# board.net
KiCad netlist of a schematic drawn in EAGLE
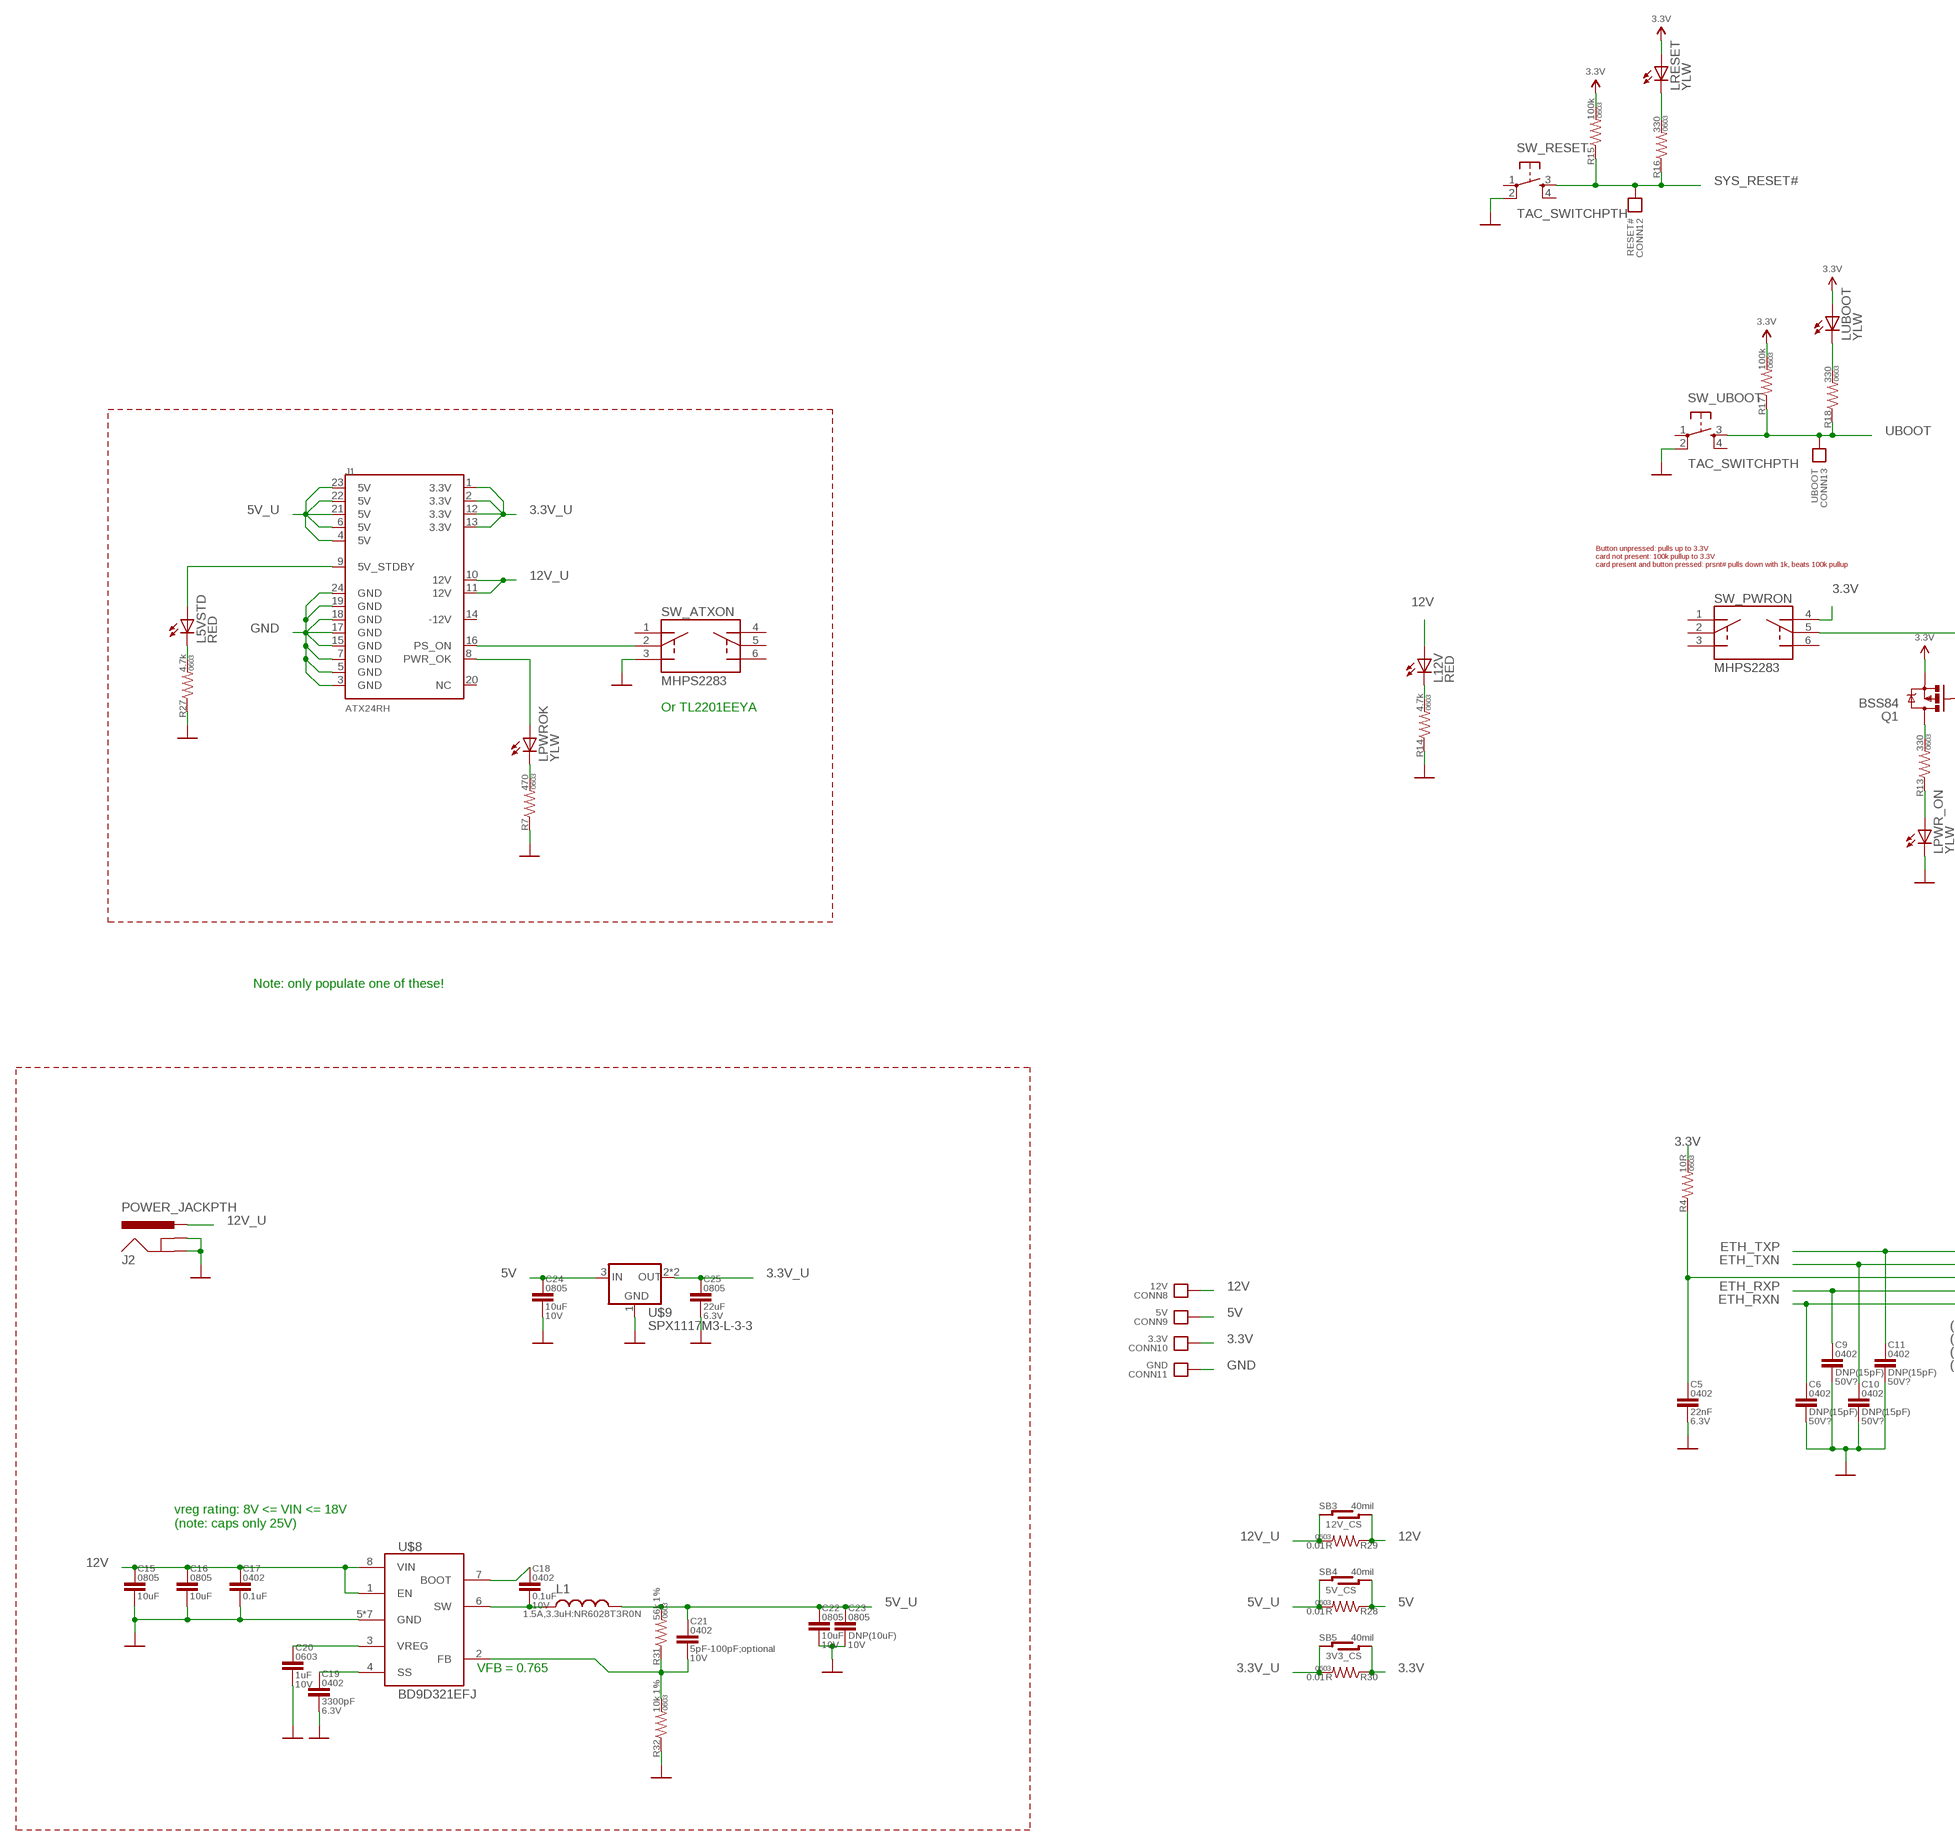
[diagram p0: schematic, sheet 1, part 1 of 2]
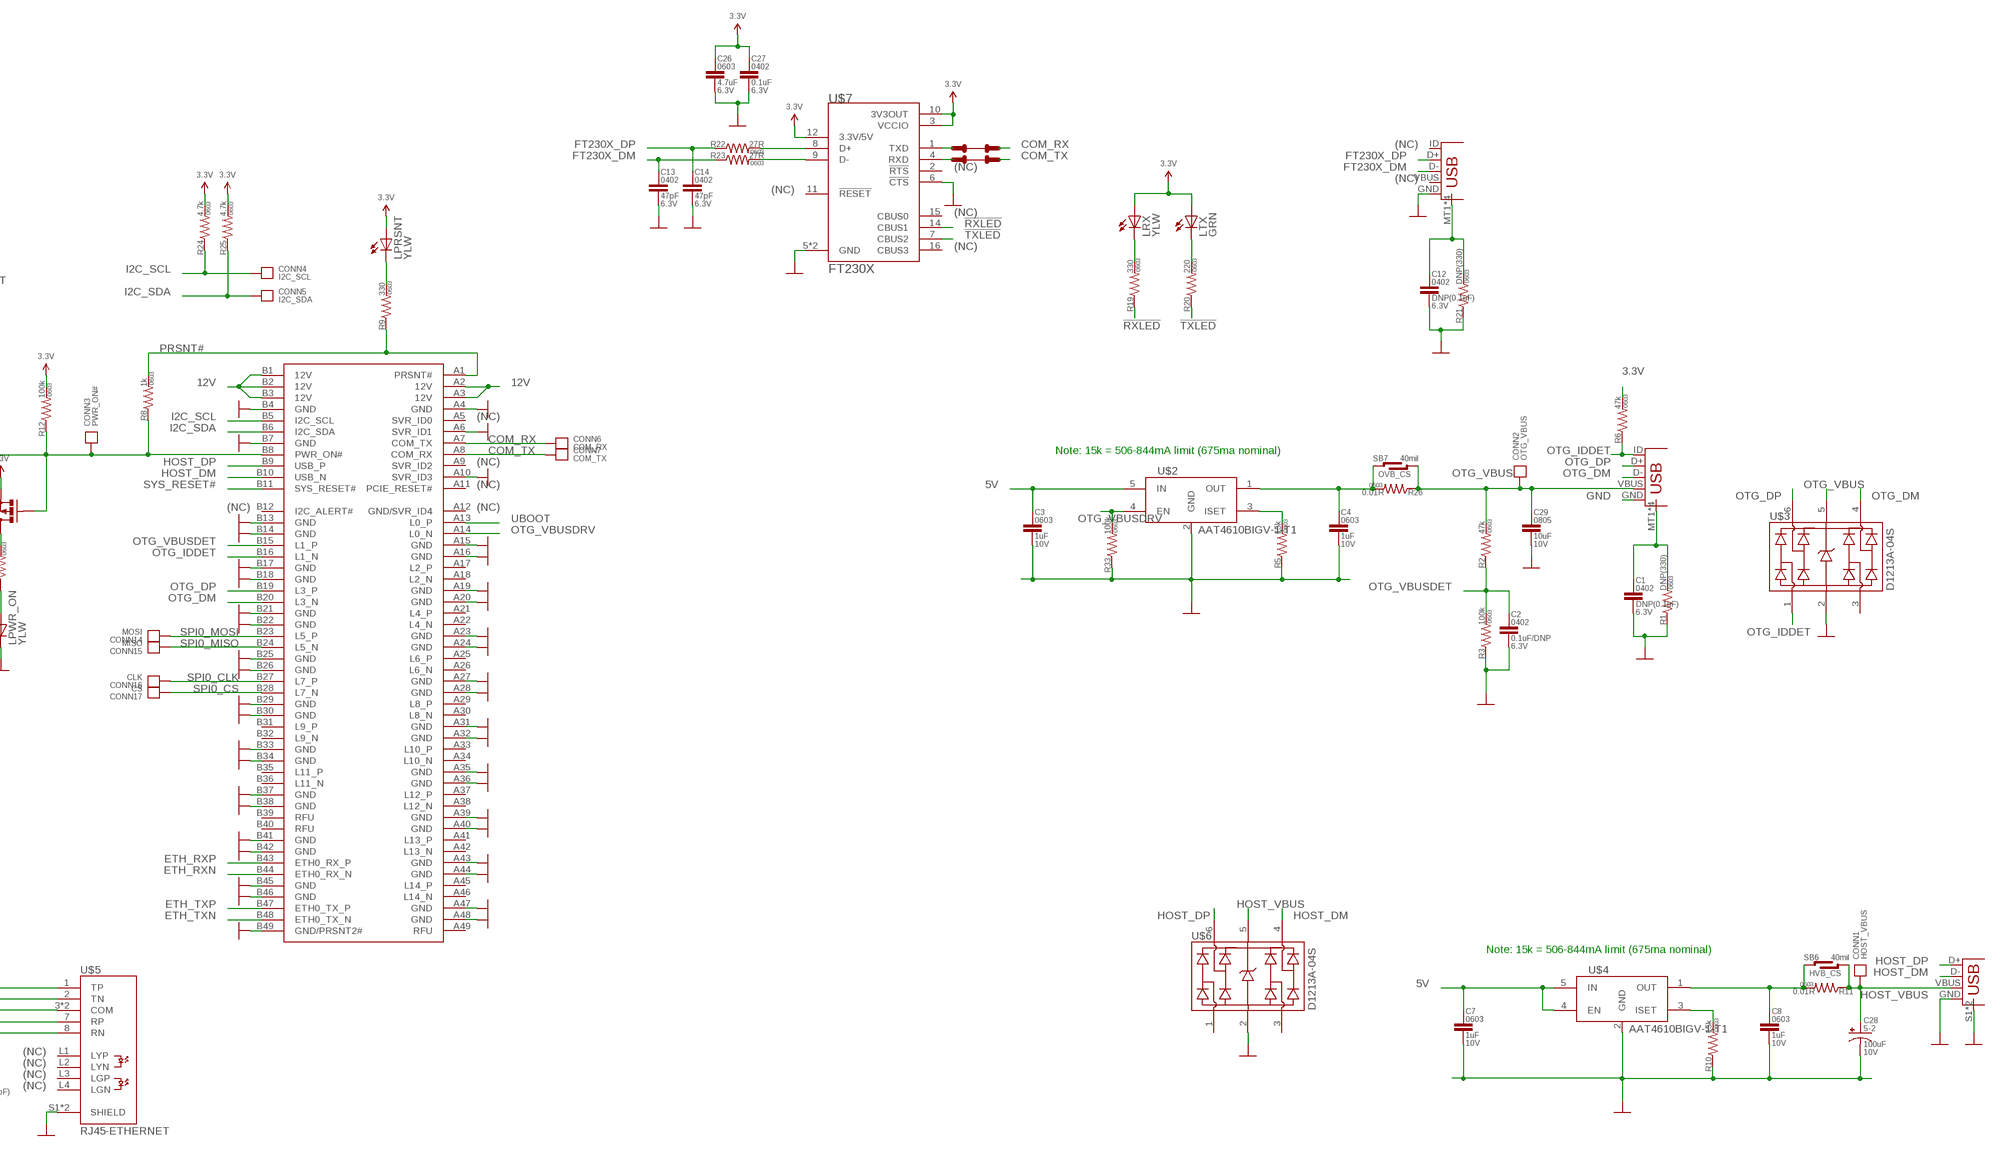
[diagram p1: schematic, sheet 1, part 2 of 2]

(export (version "E")
  (design (tool "Eeschema 10.0.6"))
  (components
    (comp (ref "C1")
      (value "DNP(0.1uF)")
      (footprint "eagle-import:0402-CAP")
      (fields (field (name "VOLTAGE") "6.3V"))
      (libsource (lib "eagle-import") (part "CAP0402-CAP"))
    )
    (comp (ref "C2")
      (value "0.1uF/DNP")
      (footprint "eagle-import:0402-CAP")
      (fields (field (name "VOLTAGE") "6.3V"))
      (libsource (lib "eagle-import") (part "CAP0402-CAP"))
    )
    (comp (ref "C3")
      (value "1uF")
      (footprint "eagle-import:0603-CAP")
      (fields (field (name "VOLTAGE") "6.3V") (field (name "VOLTAGE_1") "10V"))
      (libsource (lib "eagle-import") (part "CAP0603"))
    )
    (comp (ref "C4")
      (value "1uF")
      (footprint "eagle-import:0603-CAP")
      (fields (field (name "VOLTAGE") "6.3V") (field (name "VOLTAGE_1") "10V"))
      (libsource (lib "eagle-import") (part "CAP0603"))
    )
    (comp (ref "C5")
      (value "22nF")
      (footprint "eagle-import:0402-CAP")
      (fields (field (name "VOLTAGE") "6.3V"))
      (libsource (lib "eagle-import") (part "CAP0402-CAP"))
    )
    (comp (ref "C6")
      (value "DNP(15pF)")
      (footprint "eagle-import:0402-CAP")
      (fields (field (name "VOLTAGE") "6.3V") (field (name "VOLTAGE_1") "50V?"))
      (libsource (lib "eagle-import") (part "CAP0402-CAP"))
    )
    (comp (ref "C7")
      (value "1uF")
      (footprint "eagle-import:0603-CAP")
      (fields (field (name "VOLTAGE") "6.3V") (field (name "VOLTAGE_1") "10V"))
      (libsource (lib "eagle-import") (part "CAP0603"))
    )
    (comp (ref "C8")
      (value "1uF")
      (footprint "eagle-import:0603-CAP")
      (fields (field (name "VOLTAGE") "6.3V") (field (name "VOLTAGE_1") "10V"))
      (libsource (lib "eagle-import") (part "CAP0603"))
    )
    (comp (ref "C9")
      (value "DNP(15pF)")
      (footprint "eagle-import:0402-CAP")
      (fields (field (name "VOLTAGE") "6.3V") (field (name "VOLTAGE_1") "50V?"))
      (libsource (lib "eagle-import") (part "CAP0402-CAP"))
    )
    (comp (ref "C10")
      (value "DNP(15pF)")
      (footprint "eagle-import:0402-CAP")
      (fields (field (name "VOLTAGE") "6.3V") (field (name "VOLTAGE_1") "50V?"))
      (libsource (lib "eagle-import") (part "CAP0402-CAP"))
    )
    (comp (ref "C11")
      (value "DNP(15pF)")
      (footprint "eagle-import:0402-CAP")
      (fields (field (name "VOLTAGE") "6.3V") (field (name "VOLTAGE_1") "50V?"))
      (libsource (lib "eagle-import") (part "CAP0402-CAP"))
    )
    (comp (ref "C12")
      (value "DNP(0.1uF)")
      (footprint "eagle-import:0402-CAP")
      (fields (field (name "VOLTAGE") "6.3V"))
      (libsource (lib "eagle-import") (part "CAP0402-CAP"))
    )
    (comp (ref "C13")
      (value "47pF")
      (footprint "eagle-import:0402-CAP")
      (fields (field (name "VOLTAGE") "6.3V"))
      (libsource (lib "eagle-import") (part "CAP0402-CAP"))
    )
    (comp (ref "C14")
      (value "47pF")
      (footprint "eagle-import:0402-CAP")
      (fields (field (name "VOLTAGE") "6.3V"))
      (libsource (lib "eagle-import") (part "CAP0402-CAP"))
    )
    (comp (ref "C15")
      (value "10uF")
      (footprint "eagle-import:0805")
      (fields (field (name "VOLTAGE") "6.3V") (field (name "VOLTAGE_1") "25V"))
      (libsource (lib "eagle-import") (part "CAP0805"))
    )
    (comp (ref "C16")
      (value "10uF")
      (footprint "eagle-import:0805")
      (fields (field (name "VOLTAGE") "6.3V") (field (name "VOLTAGE_1") "25V"))
      (libsource (lib "eagle-import") (part "CAP0805"))
    )
    (comp (ref "C17")
      (value "0.1uF")
      (footprint "eagle-import:0402-CAP")
      (fields (field (name "VOLTAGE") "6.3V") (field (name "VOLTAGE_1") "25V"))
      (libsource (lib "eagle-import") (part "CAP0402-CAP"))
    )
    (comp (ref "C18")
      (value "0.1uF")
      (footprint "eagle-import:0402-CAP")
      (fields (field (name "VOLTAGE") "6.3V") (field (name "VOLTAGE_1") "10V"))
      (libsource (lib "eagle-import") (part "CAP0402-CAP"))
    )
    (comp (ref "C19")
      (value "3300pF")
      (footprint "eagle-import:0402-CAP")
      (fields (field (name "VOLTAGE") "6.3V"))
      (libsource (lib "eagle-import") (part "CAP0402-CAP"))
    )
    (comp (ref "C20")
      (value "1uF")
      (footprint "eagle-import:0603-CAP")
      (fields (field (name "VOLTAGE") "6.3V") (field (name "VOLTAGE_1") "10V"))
      (libsource (lib "eagle-import") (part "CAP0603"))
    )
    (comp (ref "C21")
      (value "5pF-100pF;optional")
      (footprint "eagle-import:0402-CAP")
      (fields (field (name "VOLTAGE") "6.3V") (field (name "VOLTAGE_1") "10V"))
      (libsource (lib "eagle-import") (part "CAP0402-CAP"))
    )
    (comp (ref "C22")
      (value "10uF")
      (footprint "eagle-import:0805")
      (fields (field (name "VOLTAGE") "6.3V") (field (name "VOLTAGE_1") "10V"))
      (libsource (lib "eagle-import") (part "CAP0805"))
    )
    (comp (ref "C23")
      (value "DNP(10uF)")
      (footprint "eagle-import:0805")
      (fields (field (name "VOLTAGE") "6.3V") (field (name "VOLTAGE_1") "10V"))
      (libsource (lib "eagle-import") (part "CAP0805"))
    )
    (comp (ref "C24")
      (value "10uF")
      (footprint "eagle-import:0805")
      (fields (field (name "VOLTAGE") "6.3V") (field (name "VOLTAGE_1") "10V"))
      (libsource (lib "eagle-import") (part "CAP0805"))
    )
    (comp (ref "C25")
      (value "22uF")
      (footprint "eagle-import:0805")
      (fields (field (name "VOLTAGE") "6.3V"))
      (libsource (lib "eagle-import") (part "CAP0805"))
    )
    (comp (ref "C26")
      (value "4.7uF")
      (footprint "eagle-import:0603-CAP")
      (fields (field (name "VOLTAGE") "6.3V"))
      (libsource (lib "eagle-import") (part "CAP0603"))
    )
    (comp (ref "C27")
      (value "0.1uF")
      (footprint "eagle-import:0402-CAP")
      (fields (field (name "VOLTAGE") "6.3V"))
      (libsource (lib "eagle-import") (part "CAP0402-CAP"))
    )
    (comp (ref "C28")
      (value "100uF")
      (footprint "eagle-import:CAP-5-2")
      (fields (field (name "VOLTAGE") "6.3V") (field (name "VOLTAGE_1") "10V"))
      (libsource (lib "eagle-import") (part "CAP_POLPTH-5-2"))
    )
    (comp (ref "C29")
      (value "10uF")
      (footprint "eagle-import:0805")
      (fields (field (name "VOLTAGE") "6.3V") (field (name "VOLTAGE_1") "10V"))
      (libsource (lib "eagle-import") (part "CAP0805"))
    )
    (comp (ref "CONN1")
      (value "HOST_VBUS")
      (footprint "eagle-import:HOLE_22AWG")
      (libsource (lib "eagle-import") (part "CONNECTOR22AWG"))
    )
    (comp (ref "CONN2")
      (value "OTG_VBUS")
      (footprint "eagle-import:HOLE_22AWG")
      (libsource (lib "eagle-import") (part "CONNECTOR22AWG"))
    )
    (comp (ref "CONN3")
      (value "PWR_ON#")
      (footprint "eagle-import:HOLE_22AWG")
      (libsource (lib "eagle-import") (part "CONNECTOR22AWG"))
    )
    (comp (ref "CONN4")
      (value "I2C_SCL")
      (footprint "eagle-import:HOLE_22AWG")
      (libsource (lib "eagle-import") (part "CONNECTOR22AWG"))
    )
    (comp (ref "CONN5")
      (value "I2C_SDA")
      (footprint "eagle-import:HOLE_22AWG")
      (libsource (lib "eagle-import") (part "CONNECTOR22AWG"))
    )
    (comp (ref "CONN6")
      (value "COM_RX")
      (footprint "eagle-import:HOLE_22AWG")
      (libsource (lib "eagle-import") (part "CONNECTOR22AWG"))
    )
    (comp (ref "CONN7")
      (value "COM_TX")
      (footprint "eagle-import:HOLE_22AWG")
      (libsource (lib "eagle-import") (part "CONNECTOR22AWG"))
    )
    (comp (ref "CONN8")
      (value "12V")
      (footprint "eagle-import:HOLE_22AWG")
      (libsource (lib "eagle-import") (part "CONNECTOR22AWG"))
    )
    (comp (ref "CONN9")
      (value "5V")
      (footprint "eagle-import:HOLE_22AWG")
      (libsource (lib "eagle-import") (part "CONNECTOR22AWG"))
    )
    (comp (ref "CONN10")
      (value "3.3V")
      (footprint "eagle-import:HOLE_22AWG")
      (libsource (lib "eagle-import") (part "CONNECTOR22AWG"))
    )
    (comp (ref "CONN11")
      (value "GND")
      (footprint "eagle-import:HOLE_22AWG")
      (libsource (lib "eagle-import") (part "CONNECTOR22AWG"))
    )
    (comp (ref "CONN12")
      (value "RESET#")
      (footprint "eagle-import:HOLE_22AWG")
      (libsource (lib "eagle-import") (part "CONNECTOR22AWG"))
    )
    (comp (ref "CONN13")
      (value "UBOOT")
      (footprint "eagle-import:HOLE_22AWG")
      (libsource (lib "eagle-import") (part "CONNECTOR22AWG"))
    )
    (comp (ref "CONN14")
      (value "MOSI")
      (footprint "eagle-import:HOLE_22AWG")
      (libsource (lib "eagle-import") (part "CONNECTOR22AWG"))
    )
    (comp (ref "CONN15")
      (value "MISO")
      (footprint "eagle-import:HOLE_22AWG")
      (libsource (lib "eagle-import") (part "CONNECTOR22AWG"))
    )
    (comp (ref "CONN16")
      (value "CLK")
      (footprint "eagle-import:HOLE_22AWG")
      (libsource (lib "eagle-import") (part "CONNECTOR22AWG"))
    )
    (comp (ref "CONN17")
      (value "CS")
      (footprint "eagle-import:HOLE_22AWG")
      (libsource (lib "eagle-import") (part "CONNECTOR22AWG"))
    )
    (comp (ref "J1")
      (value "ATX24RH")
      (footprint "eagle-import:ATX24_RIGHT_ANGLE")
      (libsource (lib "eagle-import") (part "ATX24RH"))
    )
    (comp (ref "J2")
      (value "POWER_JACKPTH")
      (footprint "eagle-import:POWER_JACK_PTH")
      (libsource (lib "eagle-import") (part "POWER_JACKPTH"))
    )
    (comp (ref "JP1")
      (value "USB-IDMICRO")
      (footprint "eagle-import:USB-MICRO")
      (libsource (lib "eagle-import") (part "USB-IDMICRO"))
    )
    (comp (ref "JP2")
      (value "USB-IDMICRO")
      (footprint "eagle-import:USB-MICRO")
      (libsource (lib "eagle-import") (part "USB-IDMICRO"))
    )
    (comp (ref "JP3")
      (value "USBA-FEMALE-TH")
      (footprint "eagle-import:USB-A-SOCKET-TH")
      (libsource (lib "eagle-import") (part "USBA-FEMALE-TH"))
    )
    (comp (ref "L1")
      (value "1.5A,3.3uH:NR6028T3R0N")
      (footprint "eagle-import:NR60XX")
      (libsource (lib "eagle-import") (part "INDUCTORNR60XX"))
    )
    (comp (ref "L5VSTD")
      (value "RED")
      (footprint "eagle-import:0603_LED")
      (libsource (lib "eagle-import") (part "LED0603"))
    )
    (comp (ref "L12V")
      (value "RED")
      (footprint "eagle-import:0603_LED")
      (libsource (lib "eagle-import") (part "LED0603"))
    )
    (comp (ref "LPRSNT")
      (value "YLW")
      (footprint "eagle-import:0603_LED")
      (libsource (lib "eagle-import") (part "LED0603"))
    )
    (comp (ref "LPWROK")
      (value "YLW")
      (footprint "eagle-import:0603_LED")
      (libsource (lib "eagle-import") (part "LED0603"))
    )
    (comp (ref "LPWR_ON")
      (value "YLW")
      (footprint "eagle-import:0603_LED")
      (libsource (lib "eagle-import") (part "LED0603"))
    )
    (comp (ref "LRESET")
      (value "YLW")
      (footprint "eagle-import:0603_LED")
      (libsource (lib "eagle-import") (part "LED0603"))
    )
    (comp (ref "LRX")
      (value "YLW")
      (footprint "eagle-import:0603_LED")
      (libsource (lib "eagle-import") (part "LED0603"))
    )
    (comp (ref "LTX")
      (value "GRN")
      (footprint "eagle-import:0603_LED")
      (libsource (lib "eagle-import") (part "LED0603"))
    )
    (comp (ref "LUBOOT")
      (value "YLW")
      (footprint "eagle-import:0603_LED")
      (libsource (lib "eagle-import") (part "LED0603"))
    )
    (comp (ref "Q1")
      (value "BSS84")
      (footprint "eagle-import:SOT23-3")
      (libsource (lib "eagle-import") (part "MOSFET-PCHANNELSMD"))
    )
    (comp (ref "R1")
      (value "DNP(330)")
      (footprint "eagle-import:0603-RES")
      (libsource (lib "eagle-import") (part "RESISTOR0603"))
    )
    (comp (ref "R2")
      (value "47k")
      (footprint "eagle-import:0603-RES")
      (libsource (lib "eagle-import") (part "RESISTOR0603"))
    )
    (comp (ref "R3")
      (value "100k")
      (footprint "eagle-import:0603-RES")
      (libsource (lib "eagle-import") (part "RESISTOR0603"))
    )
    (comp (ref "R4")
      (value "10R")
      (footprint "eagle-import:0603-RES")
      (libsource (lib "eagle-import") (part "RESISTOR0603"))
    )
    (comp (ref "R5")
      (value "15k")
      (footprint "eagle-import:0603-RES")
      (libsource (lib "eagle-import") (part "RESISTOR0603"))
    )
    (comp (ref "R6")
      (value "47k")
      (footprint "eagle-import:0603-RES")
      (libsource (lib "eagle-import") (part "RESISTOR0603"))
    )
    (comp (ref "R7")
      (value "470")
      (footprint "eagle-import:0603-RES")
      (libsource (lib "eagle-import") (part "RESISTOR0603"))
    )
    (comp (ref "R8")
      (value "1k")
      (footprint "eagle-import:0603-RES")
      (libsource (lib "eagle-import") (part "RESISTOR0603"))
    )
    (comp (ref "R9")
      (value "330")
      (footprint "eagle-import:0603-RES")
      (libsource (lib "eagle-import") (part "RESISTOR0603"))
    )
    (comp (ref "R10")
      (value "15k")
      (footprint "eagle-import:0603-RES")
      (libsource (lib "eagle-import") (part "RESISTOR0603"))
    )
    (comp (ref "R11")
      (value "0.01R")
      (footprint "eagle-import:0603-RES")
      (libsource (lib "eagle-import") (part "RESISTOR0603"))
    )
    (comp (ref "R12")
      (value "100k")
      (footprint "eagle-import:0603-RES")
      (libsource (lib "eagle-import") (part "RESISTOR0603"))
    )
    (comp (ref "R13")
      (value "330")
      (footprint "eagle-import:0603-RES")
      (libsource (lib "eagle-import") (part "RESISTOR0603"))
    )
    (comp (ref "R14")
      (value "4.7k")
      (footprint "eagle-import:0603-RES")
      (libsource (lib "eagle-import") (part "RESISTOR0603"))
    )
    (comp (ref "R15")
      (value "100k")
      (footprint "eagle-import:0603-RES")
      (libsource (lib "eagle-import") (part "RESISTOR0603"))
    )
    (comp (ref "R16")
      (value "330")
      (footprint "eagle-import:0603-RES")
      (libsource (lib "eagle-import") (part "RESISTOR0603"))
    )
    (comp (ref "R17")
      (value "100k")
      (footprint "eagle-import:0603-RES")
      (libsource (lib "eagle-import") (part "RESISTOR0603"))
    )
    (comp (ref "R18")
      (value "330")
      (footprint "eagle-import:0603-RES")
      (libsource (lib "eagle-import") (part "RESISTOR0603"))
    )
    (comp (ref "R19")
      (value "330")
      (footprint "eagle-import:0603-RES")
      (libsource (lib "eagle-import") (part "RESISTOR0603"))
    )
    (comp (ref "R20")
      (value "220")
      (footprint "eagle-import:0603-RES")
      (libsource (lib "eagle-import") (part "RESISTOR0603"))
    )
    (comp (ref "R21")
      (value "DNP(330)")
      (footprint "eagle-import:0603-RES")
      (libsource (lib "eagle-import") (part "RESISTOR0603"))
    )
    (comp (ref "R22")
      (value "27R")
      (footprint "eagle-import:0603-RES")
      (libsource (lib "eagle-import") (part "RESISTOR0603"))
    )
    (comp (ref "R23")
      (value "27R")
      (footprint "eagle-import:0603-RES")
      (libsource (lib "eagle-import") (part "RESISTOR0603"))
    )
    (comp (ref "R24")
      (value "4.7k")
      (footprint "eagle-import:0603-RES")
      (libsource (lib "eagle-import") (part "RESISTOR0603"))
    )
    (comp (ref "R25")
      (value "4.7k")
      (footprint "eagle-import:0603-RES")
      (libsource (lib "eagle-import") (part "RESISTOR0603"))
    )
    (comp (ref "R26")
      (value "0.01R")
      (footprint "eagle-import:0603-RES")
      (libsource (lib "eagle-import") (part "RESISTOR0603"))
    )
    (comp (ref "R27")
      (value "4.7k")
      (footprint "eagle-import:0603-RES")
      (libsource (lib "eagle-import") (part "RESISTOR0603"))
    )
    (comp (ref "R28")
      (value "0.01R")
      (footprint "eagle-import:0603-RES")
      (libsource (lib "eagle-import") (part "RESISTOR0603"))
    )
    (comp (ref "R29")
      (value "0.01R")
      (footprint "eagle-import:0603-RES")
      (libsource (lib "eagle-import") (part "RESISTOR0603"))
    )
    (comp (ref "R30")
      (value "0.01R")
      (footprint "eagle-import:0603-RES")
      (libsource (lib "eagle-import") (part "RESISTOR0603"))
    )
    (comp (ref "R31")
      (value "56k 1%")
      (footprint "eagle-import:0603-RES")
      (libsource (lib "eagle-import") (part "RESISTOR0603"))
    )
    (comp (ref "R32")
      (value "10k 1%")
      (footprint "eagle-import:0603-RES")
      (libsource (lib "eagle-import") (part "RESISTOR0603"))
    )
    (comp (ref "R33")
      (value "100k")
      (footprint "eagle-import:0603-RES")
      (libsource (lib "eagle-import") (part "RESISTOR0603"))
    )
    (comp (ref "SB1")
      (value "RX")
      (footprint "eagle-import:TRACE-CUT")
      (libsource (lib "eagle-import") (part "TRACE-CUT"))
    )
    (comp (ref "SB2")
      (value "TX")
      (footprint "eagle-import:TRACE-CUT")
      (libsource (lib "eagle-import") (part "TRACE-CUT"))
    )
    (comp (ref "SB3")
      (value "12V_CS")
      (footprint "eagle-import:SOLDER-BRIDGE-OPEN-LARGE")
      (libsource (lib "eagle-import") (part "SOLDER-BRIDGEOPEN-WIDE"))
    )
    (comp (ref "SB4")
      (value "5V_CS")
      (footprint "eagle-import:SOLDER-BRIDGE-OPEN-LARGE")
      (libsource (lib "eagle-import") (part "SOLDER-BRIDGEOPEN-WIDE"))
    )
    (comp (ref "SB5")
      (value "3V3_CS")
      (footprint "eagle-import:SOLDER-BRIDGE-OPEN-LARGE")
      (libsource (lib "eagle-import") (part "SOLDER-BRIDGEOPEN-WIDE"))
    )
    (comp (ref "SB6")
      (value "HVB_CS")
      (footprint "eagle-import:SOLDER-BRIDGE-OPEN-LARGE")
      (libsource (lib "eagle-import") (part "SOLDER-BRIDGEOPEN-WIDE"))
    )
    (comp (ref "SB7")
      (value "OVB_CS")
      (footprint "eagle-import:SOLDER-BRIDGE-OPEN-LARGE")
      (libsource (lib "eagle-import") (part "SOLDER-BRIDGEOPEN-WIDE"))
    )
    (comp (ref "SW_ATXON")
      (value "MHPS2283")
      (footprint "eagle-import:PUSHBUTTON-2.5-5.4")
      (libsource (lib "eagle-import") (part "SWITCH_DPDTPUSHBUTTON"))
    )
    (comp (ref "SW_PWRON")
      (value "MHPS2283")
      (footprint "eagle-import:PUSHBUTTON-2.5-5.4")
      (libsource (lib "eagle-import") (part "SWITCH_DPDTPUSHBUTTON"))
    )
    (comp (ref "SW_RESET")
      (value "TAC_SWITCHPTH")
      (footprint "eagle-import:TACTILE-PTH")
      (libsource (lib "eagle-import") (part "TAC_SWITCHPTH"))
    )
    (comp (ref "SW_UBOOT")
      (value "TAC_SWITCHPTH")
      (footprint "eagle-import:TACTILE-PTH")
      (libsource (lib "eagle-import") (part "TAC_SWITCHPTH"))
    )
    (comp (ref "U$1")
      (value "CVN-V1CONN")
      (footprint "eagle-import:CVN-V1-CONN")
      (libsource (lib "eagle-import") (part "CVN-V1CONN"))
    )
    (comp (ref "U$2")
      (value "AAT4610BIGV-1-T1")
      (footprint "eagle-import:SOT23-5")
      (libsource (lib "eagle-import") (part "LOAD_SWITCH_ILIMIT"))
    )
    (comp (ref "U$3")
      (value "D1213A-04S")
      (footprint "eagle-import:SOT363")
      (libsource (lib "eagle-import") (part "TVS_ARRAY"))
    )
    (comp (ref "U$4")
      (value "AAT4610BIGV-1-T1")
      (footprint "eagle-import:SOT23-5")
      (libsource (lib "eagle-import") (part "LOAD_SWITCH_ILIMIT"))
    )
    (comp (ref "U$5")
      (value "RJ45-ETHERNET")
      (footprint "eagle-import:RJ45")
      (libsource (lib "eagle-import") (part "RJ45-ETHERNET"))
    )
    (comp (ref "U$6")
      (value "D1213A-04S")
      (footprint "eagle-import:SOT363")
      (libsource (lib "eagle-import") (part "TVS_ARRAY"))
    )
    (comp (ref "U$7")
      (value "FT230X")
      (footprint "eagle-import:TSSOP16")
      (libsource (lib "eagle-import") (part "FT230X"))
    )
    (comp (ref "U$8")
      (value "BD9D321EFJ")
      (footprint "eagle-import:HTSOP8")
      (libsource (lib "eagle-import") (part "BD9D321EFJ"))
    )
    (comp (ref "U$9")
      (value "SPX1117M3-L-3-3")
      (footprint "eagle-import:SOT223")
      (libsource (lib "eagle-import") (part "VREGSOT223"))
    )
  )
  (nets
    (net (code "1") (name "/3.3V_U") (class "Default")
      (node (ref "C25") (pin "1") (pinfunction "1_1") (pintype "passive"))
      (node (ref "J1") (pin "1") (pinfunction "3.3V_1") (pintype "bidirectional"))
      (node (ref "J1") (pin "12") (pinfunction "3.3V_12") (pintype "bidirectional"))
      (node (ref "J1") (pin "13") (pinfunction "3.3V_13") (pintype "bidirectional"))
      (node (ref "J1") (pin "2") (pinfunction "3.3V_2") (pintype "bidirectional"))
      (node (ref "R30") (pin "2") (pinfunction "2_2") (pintype "passive"))
      (node (ref "SB5") (pin "L1") (pinfunction "P$1_L1") (pintype "passive"))
      (node (ref "SB5") (pin "L2") (pinfunction "P$1_L2") (pintype "passive"))
      (node (ref "U$9") (pin "2") (pinfunction "OUT_2") (pintype "passive"))
      (node (ref "U$9") (pin "4") (pinfunction "OUT_4") (pintype "passive"))
    )
    (net (code "2") (name "/5V") (class "Default")
      (node (ref "C24") (pin "1") (pinfunction "1_1") (pintype "passive"))
      (node (ref "C3") (pin "1") (pinfunction "1_1") (pintype "passive"))
      (node (ref "C7") (pin "1") (pinfunction "1_1") (pintype "passive"))
      (node (ref "CONN9") (pin "P") (pinfunction "P_P") (pintype "bidirectional"))
      (node (ref "R28") (pin "1") (pinfunction "1_1") (pintype "passive"))
      (node (ref "SB4") (pin "R1") (pinfunction "P$2_R1") (pintype "passive"))
      (node (ref "SB4") (pin "R2") (pinfunction "P$2_R2") (pintype "passive"))
      (node (ref "U$2") (pin "5") (pinfunction "IN_5") (pintype "bidirectional"))
      (node (ref "U$4") (pin "4") (pinfunction "EN_4") (pintype "bidirectional"))
      (node (ref "U$4") (pin "5") (pinfunction "IN_5") (pintype "bidirectional"))
      (node (ref "U$9") (pin "3") (pinfunction "IN_3") (pintype "input"))
    )
    (net (code "3") (name "/5V_U") (class "Default")
      (node (ref "C21") (pin "1") (pinfunction "1_1") (pintype "passive"))
      (node (ref "C22") (pin "1") (pinfunction "1_1") (pintype "passive"))
      (node (ref "C23") (pin "1") (pinfunction "1_1") (pintype "passive"))
      (node (ref "J1") (pin "21") (pinfunction "5V_21") (pintype "bidirectional"))
      (node (ref "J1") (pin "22") (pinfunction "5V_22") (pintype "bidirectional"))
      (node (ref "J1") (pin "23") (pinfunction "5V_23") (pintype "bidirectional"))
      (node (ref "J1") (pin "4") (pinfunction "5V_4") (pintype "bidirectional"))
      (node (ref "J1") (pin "6") (pinfunction "5V_6") (pintype "bidirectional"))
      (node (ref "L1") (pin "P$2") (pinfunction "2_P$2") (pintype "passive"))
      (node (ref "R28") (pin "2") (pinfunction "2_2") (pintype "passive"))
      (node (ref "R31") (pin "2") (pinfunction "2_2") (pintype "passive"))
      (node (ref "SB4") (pin "L1") (pinfunction "P$1_L1") (pintype "passive"))
      (node (ref "SB4") (pin "L2") (pinfunction "P$1_L2") (pintype "passive"))
    )
    (net (code "4") (name "/12V") (class "Default")
      (node (ref "C15") (pin "1") (pinfunction "1_1") (pintype "passive"))
      (node (ref "C16") (pin "1") (pinfunction "1_1") (pintype "passive"))
      (node (ref "C17") (pin "1") (pinfunction "1_1") (pintype "passive"))
      (node (ref "CONN8") (pin "P") (pinfunction "P_P") (pintype "bidirectional"))
      (node (ref "L12V") (pin "A") (pinfunction "A_A") (pintype "passive"))
      (node (ref "R29") (pin "1") (pinfunction "1_1") (pintype "passive"))
      (node (ref "SB3") (pin "R1") (pinfunction "P$2_R1") (pintype "passive"))
      (node (ref "SB3") (pin "R2") (pinfunction "P$2_R2") (pintype "passive"))
      (node (ref "U$1") (pin "A2") (pinfunction "12V_A2") (pintype "input"))
      (node (ref "U$1") (pin "A3") (pinfunction "12V_A3") (pintype "input"))
      (node (ref "U$1") (pin "B1") (pinfunction "12V_B1") (pintype "input"))
      (node (ref "U$1") (pin "B2") (pinfunction "12V_B2") (pintype "input"))
      (node (ref "U$1") (pin "B3") (pinfunction "12V_B3") (pintype "input"))
      (node (ref "U$8") (pin "1") (pinfunction "EN_1") (pintype "input"))
      (node (ref "U$8") (pin "8") (pinfunction "VIN_8") (pintype "input"))
    )
    (net (code "5") (name "/12V_U") (class "Default")
      (node (ref "J1") (pin "10") (pinfunction "12V_10") (pintype "bidirectional"))
      (node (ref "J1") (pin "11") (pinfunction "12V_11") (pintype "bidirectional"))
      (node (ref "J2") (pin "PWR") (pinfunction "PWR_PWR") (pintype "bidirectional"))
      (node (ref "R29") (pin "2") (pinfunction "2_2") (pintype "passive"))
      (node (ref "SB3") (pin "L1") (pinfunction "P$1_L1") (pintype "passive"))
      (node (ref "SB3") (pin "L2") (pinfunction "P$1_L2") (pintype "passive"))
    )
    (net (code "6") (name "/COM_RX") (class "Default")
      (node (ref "CONN6") (pin "P") (pinfunction "P_P") (pintype "bidirectional"))
      (node (ref "SB1") (pin "R1") (pinfunction "P$2_R1") (pintype "passive"))
      (node (ref "U$1") (pin "A7") (pinfunction "COM_TX_A7") (pintype "bidirectional"))
    )
    (net (code "7") (name "/COM_TX") (class "Default")
      (node (ref "CONN7") (pin "P") (pinfunction "P_P") (pintype "bidirectional"))
      (node (ref "SB2") (pin "R1") (pinfunction "P$2_R1") (pintype "passive"))
      (node (ref "U$1") (pin "A8") (pinfunction "COM_RX_A8") (pintype "bidirectional"))
    )
    (net (code "8") (name "/ETH_RXN") (class "Default")
      (node (ref "C6") (pin "1") (pinfunction "1_1") (pintype "passive"))
      (node (ref "U$1") (pin "B44") (pinfunction "ETH0_RX_N_B44") (pintype "bidirectional"))
      (node (ref "U$5") (pin "8") (pinfunction "RN_8") (pintype "bidirectional"))
    )
    (net (code "9") (name "/ETH_RXP") (class "Default")
      (node (ref "C9") (pin "1") (pinfunction "1_1") (pintype "passive"))
      (node (ref "U$1") (pin "B43") (pinfunction "ETH0_RX_P_B43") (pintype "bidirectional"))
      (node (ref "U$5") (pin "7") (pinfunction "RP_7") (pintype "bidirectional"))
    )
    (net (code "10") (name "/ETH_TXN") (class "Default")
      (node (ref "C10") (pin "1") (pinfunction "1_1") (pintype "passive"))
      (node (ref "U$1") (pin "B48") (pinfunction "ETH0_TX_N_B48") (pintype "bidirectional"))
      (node (ref "U$5") (pin "2") (pinfunction "TN_2") (pintype "bidirectional"))
    )
    (net (code "11") (name "/ETH_TXP") (class "Default")
      (node (ref "C11") (pin "1") (pinfunction "1_1") (pintype "passive"))
      (node (ref "U$1") (pin "B47") (pinfunction "ETH0_TX_P_B47") (pintype "bidirectional"))
      (node (ref "U$5") (pin "1") (pinfunction "TP_1") (pintype "bidirectional"))
    )
    (net (code "12") (name "/FT230X_DM") (class "Default")
      (node (ref "C13") (pin "1") (pinfunction "1_1") (pintype "passive"))
      (node (ref "JP2") (pin "D-") (pinfunction "D-_D-") (pintype "bidirectional"))
      (node (ref "R23") (pin "1") (pinfunction "1_1") (pintype "passive"))
    )
    (net (code "13") (name "/FT230X_DP") (class "Default")
      (node (ref "C14") (pin "1") (pinfunction "1_1") (pintype "passive"))
      (node (ref "JP2") (pin "D+") (pinfunction "D+_D+") (pintype "bidirectional"))
      (node (ref "R22") (pin "1") (pinfunction "1_1") (pintype "passive"))
    )
    (net (code "14") (name "/HOST_DM") (class "Default")
      (node (ref "JP3") (pin "D-") (pinfunction "D-_D-") (pintype "bidirectional"))
      (node (ref "U$1") (pin "B10") (pinfunction "USB_N_B10") (pintype "bidirectional"))
      (node (ref "U$6") (pin "4") (pinfunction "CH3_4") (pintype "bidirectional"))
    )
    (net (code "15") (name "/HOST_DP") (class "Default")
      (node (ref "JP3") (pin "D+") (pinfunction "D+_D+") (pintype "bidirectional"))
      (node (ref "U$1") (pin "B9") (pinfunction "USB_P_B9") (pintype "bidirectional"))
      (node (ref "U$6") (pin "6") (pinfunction "CH4_6") (pintype "bidirectional"))
    )
    (net (code "16") (name "/HOST_VBUS") (class "Default")
      (node (ref "C28") (pin "1") (pinfunction "+_1") (pintype "passive"))
      (node (ref "CONN1") (pin "P") (pinfunction "P_P") (pintype "bidirectional"))
      (node (ref "JP3") (pin "VBUS") (pinfunction "VBUS_VBUS") (pintype "bidirectional"))
      (node (ref "R11") (pin "1") (pinfunction "1_1") (pintype "passive"))
      (node (ref "SB6") (pin "R1") (pinfunction "P$2_R1") (pintype "passive"))
      (node (ref "SB6") (pin "R2") (pinfunction "P$2_R2") (pintype "passive"))
      (node (ref "U$6") (pin "5") (pinfunction "VP_5") (pintype "bidirectional"))
    )
    (net (code "17") (name "/I2C_SCL") (class "Default")
      (node (ref "CONN4") (pin "P") (pinfunction "P_P") (pintype "bidirectional"))
      (node (ref "R24") (pin "1") (pinfunction "1_1") (pintype "passive"))
      (node (ref "U$1") (pin "B5") (pinfunction "I2C_SCL_B5") (pintype "bidirectional"))
    )
    (net (code "18") (name "/I2C_SDA") (class "Default")
      (node (ref "CONN5") (pin "P") (pinfunction "P_P") (pintype "bidirectional"))
      (node (ref "R25") (pin "1") (pinfunction "1_1") (pintype "passive"))
      (node (ref "U$1") (pin "B6") (pinfunction "I2C_SDA_B6") (pintype "bidirectional"))
    )
    (net (code "19") (name "/OTG_DM") (class "Default")
      (node (ref "JP1") (pin "D-") (pinfunction "D-_D-") (pintype "bidirectional"))
      (node (ref "U$1") (pin "B20") (pinfunction "L3_N_B20") (pintype "bidirectional"))
      (node (ref "U$3") (pin "4") (pinfunction "CH3_4") (pintype "bidirectional"))
    )
    (net (code "20") (name "/OTG_DP") (class "Default")
      (node (ref "JP1") (pin "D+") (pinfunction "D+_D+") (pintype "bidirectional"))
      (node (ref "U$1") (pin "B19") (pinfunction "L3_P_B19") (pintype "bidirectional"))
      (node (ref "U$3") (pin "6") (pinfunction "CH4_6") (pintype "bidirectional"))
    )
    (net (code "21") (name "/OTG_IDDET") (class "Default")
      (node (ref "JP1") (pin "ID") (pinfunction "ID_ID") (pintype "bidirectional"))
      (node (ref "R6") (pin "1") (pinfunction "1_1") (pintype "passive"))
      (node (ref "U$1") (pin "B16") (pinfunction "L1_N_B16") (pintype "bidirectional"))
      (node (ref "U$3") (pin "1") (pinfunction "CH1_1") (pintype "bidirectional"))
    )
    (net (code "22") (name "/OTG_VBUS") (class "Default")
      (node (ref "C29") (pin "1") (pinfunction "1_1") (pintype "passive"))
      (node (ref "CONN2") (pin "P") (pinfunction "P_P") (pintype "bidirectional"))
      (node (ref "JP1") (pin "VBUS") (pinfunction "VBUS_VBUS") (pintype "bidirectional"))
      (node (ref "R2") (pin "2") (pinfunction "2_2") (pintype "passive"))
      (node (ref "R26") (pin "1") (pinfunction "1_1") (pintype "passive"))
      (node (ref "SB7") (pin "R1") (pinfunction "P$2_R1") (pintype "passive"))
      (node (ref "SB7") (pin "R2") (pinfunction "P$2_R2") (pintype "passive"))
      (node (ref "U$3") (pin "5") (pinfunction "VP_5") (pintype "bidirectional"))
    )
    (net (code "23") (name "/OTG_VBUSDET") (class "Default")
      (node (ref "C2") (pin "1") (pinfunction "1_1") (pintype "passive"))
      (node (ref "R2") (pin "1") (pinfunction "1_1") (pintype "passive"))
      (node (ref "R3") (pin "2") (pinfunction "2_2") (pintype "passive"))
      (node (ref "U$1") (pin "B15") (pinfunction "L1_P_B15") (pintype "bidirectional"))
    )
    (net (code "24") (name "/OTG_VBUSDRV") (class "Default")
      (node (ref "R33") (pin "2") (pinfunction "2_2") (pintype "passive"))
      (node (ref "U$1") (pin "A14") (pinfunction "L0_N_A14") (pintype "bidirectional"))
      (node (ref "U$2") (pin "4") (pinfunction "EN_4") (pintype "bidirectional"))
    )
    (net (code "25") (name "/PRSNT#") (class "Default")
      (node (ref "R8") (pin "2") (pinfunction "2_2") (pintype "passive"))
      (node (ref "R9") (pin "1") (pinfunction "1_1") (pintype "passive"))
      (node (ref "U$1") (pin "A1") (pinfunction "PRSNT#_A1") (pintype "bidirectional"))
    )
    (net (code "26") (name "/SPI0_CLK") (class "Default")
      (node (ref "CONN16") (pin "P") (pinfunction "P_P") (pintype "bidirectional"))
      (node (ref "U$1") (pin "B27") (pinfunction "L7_P_B27") (pintype "bidirectional"))
    )
    (net (code "27") (name "/SPI0_CS") (class "Default")
      (node (ref "CONN17") (pin "P") (pinfunction "P_P") (pintype "bidirectional"))
      (node (ref "U$1") (pin "B28") (pinfunction "L7_N_B28") (pintype "bidirectional"))
    )
    (net (code "28") (name "/SPI0_MISO") (class "Default")
      (node (ref "CONN15") (pin "P") (pinfunction "P_P") (pintype "bidirectional"))
      (node (ref "U$1") (pin "B24") (pinfunction "L5_N_B24") (pintype "bidirectional"))
    )
    (net (code "29") (name "/SPI0_MOSI") (class "Default")
      (node (ref "CONN14") (pin "P") (pinfunction "P_P") (pintype "bidirectional"))
      (node (ref "U$1") (pin "B23") (pinfunction "L5_P_B23") (pintype "bidirectional"))
    )
    (net (code "30") (name "/SYS_RESET#") (class "Default")
      (node (ref "CONN12") (pin "P") (pinfunction "P_P") (pintype "bidirectional"))
      (node (ref "R15") (pin "1") (pinfunction "1_1") (pintype "passive"))
      (node (ref "R16") (pin "1") (pinfunction "1_1") (pintype "passive"))
      (node (ref "SW_RESET") (pin "3") (pinfunction "3_3") (pintype "passive"))
      (node (ref "U$1") (pin "B11") (pinfunction "SYS_RESET#_B11") (pintype "bidirectional"))
    )
    (net (code "31") (name "/UBOOT") (class "Default")
      (node (ref "CONN13") (pin "P") (pinfunction "P_P") (pintype "bidirectional"))
      (node (ref "R17") (pin "1") (pinfunction "1_1") (pintype "passive"))
      (node (ref "R18") (pin "1") (pinfunction "1_1") (pintype "passive"))
      (node (ref "SW_UBOOT") (pin "3") (pinfunction "3_3") (pintype "passive"))
      (node (ref "U$1") (pin "A13") (pinfunction "L0_P_A13") (pintype "bidirectional"))
    )
    (net (code "32") (name "/~{RXLED}") (class "Default")
      (node (ref "R19") (pin "1") (pinfunction "1_1") (pintype "passive"))
      (node (ref "U$7") (pin "14") (pinfunction "CBUS1_14") (pintype "bidirectional"))
    )
    (net (code "33") (name "/~{TXLED}") (class "Default")
      (node (ref "R20") (pin "1") (pinfunction "1_1") (pintype "passive"))
      (node (ref "U$7") (pin "7") (pinfunction "CBUS2_7") (pintype "bidirectional"))
    )
    (net (code "34") (name "3.3V") (class "Default")
      (node (ref "C26") (pin "1") (pinfunction "1_1") (pintype "passive"))
      (node (ref "C27") (pin "1") (pinfunction "1_1") (pintype "passive"))
      (node (ref "CONN10") (pin "P") (pinfunction "P_P") (pintype "bidirectional"))
      (node (ref "LPRSNT") (pin "A") (pinfunction "A_A") (pintype "passive"))
      (node (ref "LRESET") (pin "A") (pinfunction "A_A") (pintype "passive"))
      (node (ref "LRX") (pin "A") (pinfunction "A_A") (pintype "passive"))
      (node (ref "LTX") (pin "A") (pinfunction "A_A") (pintype "passive"))
      (node (ref "LUBOOT") (pin "A") (pinfunction "A_A") (pintype "passive"))
      (node (ref "Q1") (pin "2") (pinfunction "S_2") (pintype "passive"))
      (node (ref "R12") (pin "2") (pinfunction "2_2") (pintype "passive"))
      (node (ref "R15") (pin "2") (pinfunction "2_2") (pintype "passive"))
      (node (ref "R17") (pin "2") (pinfunction "2_2") (pintype "passive"))
      (node (ref "R24") (pin "2") (pinfunction "2_2") (pintype "passive"))
      (node (ref "R25") (pin "2") (pinfunction "2_2") (pintype "passive"))
      (node (ref "R30") (pin "1") (pinfunction "1_1") (pintype "passive"))
      (node (ref "R4") (pin "2") (pinfunction "2_2") (pintype "passive"))
      (node (ref "R6") (pin "2") (pinfunction "2_2") (pintype "passive"))
      (node (ref "SB5") (pin "R1") (pinfunction "P$2_R1") (pintype "passive"))
      (node (ref "SB5") (pin "R2") (pinfunction "P$2_R2") (pintype "passive"))
      (node (ref "SW_PWRON") (pin "4") (pinfunction "NC1_4") (pintype "bidirectional"))
      (node (ref "U$7") (pin "10") (pinfunction "3V3OUT_10") (pintype "bidirectional"))
      (node (ref "U$7") (pin "12") (pinfunction "3.3V/5V_12") (pintype "bidirectional"))
      (node (ref "U$7") (pin "3") (pinfunction "VCCIO_3") (pintype "bidirectional"))
    )
    (net (code "35") (name "GND") (class "Default")
      (node (ref "C1") (pin "2") (pinfunction "2_2") (pintype "passive"))
      (node (ref "C10") (pin "2") (pinfunction "2_2") (pintype "passive"))
      (node (ref "C11") (pin "2") (pinfunction "2_2") (pintype "passive"))
      (node (ref "C12") (pin "2") (pinfunction "2_2") (pintype "passive"))
      (node (ref "C13") (pin "2") (pinfunction "2_2") (pintype "passive"))
      (node (ref "C14") (pin "2") (pinfunction "2_2") (pintype "passive"))
      (node (ref "C15") (pin "2") (pinfunction "2_2") (pintype "passive"))
      (node (ref "C16") (pin "2") (pinfunction "2_2") (pintype "passive"))
      (node (ref "C17") (pin "2") (pinfunction "2_2") (pintype "passive"))
      (node (ref "C19") (pin "2") (pinfunction "2_2") (pintype "passive"))
      (node (ref "C2") (pin "2") (pinfunction "2_2") (pintype "passive"))
      (node (ref "C20") (pin "2") (pinfunction "2_2") (pintype "passive"))
      (node (ref "C22") (pin "2") (pinfunction "2_2") (pintype "passive"))
      (node (ref "C23") (pin "2") (pinfunction "2_2") (pintype "passive"))
      (node (ref "C24") (pin "2") (pinfunction "2_2") (pintype "passive"))
      (node (ref "C25") (pin "2") (pinfunction "2_2") (pintype "passive"))
      (node (ref "C26") (pin "2") (pinfunction "2_2") (pintype "passive"))
      (node (ref "C27") (pin "2") (pinfunction "2_2") (pintype "passive"))
      (node (ref "C28") (pin "2") (pinfunction "-_2") (pintype "passive"))
      (node (ref "C29") (pin "2") (pinfunction "2_2") (pintype "passive"))
      (node (ref "C3") (pin "2") (pinfunction "2_2") (pintype "passive"))
      (node (ref "C4") (pin "2") (pinfunction "2_2") (pintype "passive"))
      (node (ref "C5") (pin "2") (pinfunction "2_2") (pintype "passive"))
      (node (ref "C6") (pin "2") (pinfunction "2_2") (pintype "passive"))
      (node (ref "C7") (pin "2") (pinfunction "2_2") (pintype "passive"))
      (node (ref "C8") (pin "2") (pinfunction "2_2") (pintype "passive"))
      (node (ref "C9") (pin "2") (pinfunction "2_2") (pintype "passive"))
      (node (ref "CONN11") (pin "P") (pinfunction "P_P") (pintype "bidirectional"))
      (node (ref "J1") (pin "15") (pinfunction "GND_15") (pintype "bidirectional"))
      (node (ref "J1") (pin "17") (pinfunction "GND_17") (pintype "bidirectional"))
      (node (ref "J1") (pin "18") (pinfunction "GND_18") (pintype "bidirectional"))
      (node (ref "J1") (pin "19") (pinfunction "GND_19") (pintype "bidirectional"))
      (node (ref "J1") (pin "24") (pinfunction "GND_24") (pintype "bidirectional"))
      (node (ref "J1") (pin "3") (pinfunction "GND_3") (pintype "bidirectional"))
      (node (ref "J1") (pin "5") (pinfunction "GND_5") (pintype "bidirectional"))
      (node (ref "J1") (pin "7") (pinfunction "GND_7") (pintype "bidirectional"))
      (node (ref "J2") (pin "GND") (pinfunction "GND_GND") (pintype "bidirectional"))
      (node (ref "J2") (pin "GNDBREAK") (pinfunction "GNDBREAK_GNDBREAK") (pintype "bidirectional"))
      (node (ref "JP1") (pin "GND") (pinfunction "GND_GND") (pintype "bidirectional"))
      (node (ref "JP2") (pin "GND") (pinfunction "GND_GND") (pintype "bidirectional"))
      (node (ref "JP3") (pin "GND") (pinfunction "GND_GND") (pintype "bidirectional"))
      (node (ref "JP3") (pin "S1") (pinfunction "SHELL_S1") (pintype "bidirectional"))
      (node (ref "JP3") (pin "S2") (pinfunction "SHELL_S2") (pintype "bidirectional"))
      (node (ref "LPWR_ON") (pin "C") (pinfunction "C_C") (pintype "passive"))
      (node (ref "R1") (pin "1") (pinfunction "1_1") (pintype "passive"))
      (node (ref "R10") (pin "1") (pinfunction "1_1") (pintype "passive"))
      (node (ref "R14") (pin "1") (pinfunction "1_1") (pintype "passive"))
      (node (ref "R21") (pin "1") (pinfunction "1_1") (pintype "passive"))
      (node (ref "R27") (pin "1") (pinfunction "1_1") (pintype "passive"))
      (node (ref "R3") (pin "1") (pinfunction "1_1") (pintype "passive"))
      (node (ref "R32") (pin "1") (pinfunction "1_1") (pintype "passive"))
      (node (ref "R33") (pin "1") (pinfunction "1_1") (pintype "passive"))
      (node (ref "R5") (pin "1") (pinfunction "1_1") (pintype "passive"))
      (node (ref "R7") (pin "1") (pinfunction "1_1") (pintype "passive"))
      (node (ref "SW_ATXON") (pin "3") (pinfunction "NO0_3") (pintype "bidirectional"))
      (node (ref "SW_RESET") (pin "2") (pinfunction "2_2") (pintype "passive"))
      (node (ref "SW_UBOOT") (pin "2") (pinfunction "2_2") (pintype "passive"))
      (node (ref "U$1") (pin "A10") (pinfunction "SVR_ID3_A10") (pintype "bidirectional"))
      (node (ref "U$1") (pin "A15") (pinfunction "GND_A15") (pintype "input"))
      (node (ref "U$1") (pin "A16") (pinfunction "GND_A16") (pintype "input"))
      (node (ref "U$1") (pin "A19") (pinfunction "GND_A19") (pintype "input"))
      (node (ref "U$1") (pin "A20") (pinfunction "GND_A20") (pintype "input"))
      (node (ref "U$1") (pin "A23") (pinfunction "GND_A23") (pintype "input"))
      (node (ref "U$1") (pin "A24") (pinfunction "GND_A24") (pintype "input"))
      (node (ref "U$1") (pin "A27") (pinfunction "GND_A27") (pintype "input"))
      (node (ref "U$1") (pin "A28") (pinfunction "GND_A28") (pintype "input"))
      (node (ref "U$1") (pin "A31") (pinfunction "GND_A31") (pintype "input"))
      (node (ref "U$1") (pin "A32") (pinfunction "GND_A32") (pintype "input"))
      (node (ref "U$1") (pin "A35") (pinfunction "GND_A35") (pintype "input"))
      (node (ref "U$1") (pin "A36") (pinfunction "GND_A36") (pintype "input"))
      (node (ref "U$1") (pin "A39") (pinfunction "GND_A39") (pintype "input"))
      (node (ref "U$1") (pin "A4") (pinfunction "GND_A4") (pintype "input"))
      (node (ref "U$1") (pin "A40") (pinfunction "GND_A40") (pintype "input"))
      (node (ref "U$1") (pin "A43") (pinfunction "GND_A43") (pintype "input"))
      (node (ref "U$1") (pin "A44") (pinfunction "GND_A44") (pintype "input"))
      (node (ref "U$1") (pin "A47") (pinfunction "GND_A47") (pintype "input"))
      (node (ref "U$1") (pin "A48") (pinfunction "GND_A48") (pintype "input"))
      (node (ref "U$1") (pin "A6") (pinfunction "SVR_ID1_A6") (pintype "bidirectional"))
      (node (ref "U$1") (pin "B13") (pinfunction "GND_B13") (pintype "input"))
      (node (ref "U$1") (pin "B14") (pinfunction "GND_B14") (pintype "input"))
      (node (ref "U$1") (pin "B17") (pinfunction "GND_B17") (pintype "input"))
      (node (ref "U$1") (pin "B18") (pinfunction "GND_B18") (pintype "input"))
      (node (ref "U$1") (pin "B21") (pinfunction "GND_B21") (pintype "input"))
      (node (ref "U$1") (pin "B22") (pinfunction "GND_B22") (pintype "input"))
      (node (ref "U$1") (pin "B25") (pinfunction "GND_B25") (pintype "input"))
      (node (ref "U$1") (pin "B26") (pinfunction "GND_B26") (pintype "input"))
      (node (ref "U$1") (pin "B29") (pinfunction "GND_B29") (pintype "input"))
      (node (ref "U$1") (pin "B30") (pinfunction "GND_B30") (pintype "input"))
      (node (ref "U$1") (pin "B33") (pinfunction "GND_B33") (pintype "input"))
      (node (ref "U$1") (pin "B34") (pinfunction "GND_B34") (pintype "input"))
      (node (ref "U$1") (pin "B37") (pinfunction "GND_B37") (pintype "input"))
      (node (ref "U$1") (pin "B38") (pinfunction "GND_B38") (pintype "input"))
      (node (ref "U$1") (pin "B4") (pinfunction "GND_B4") (pintype "input"))
      (node (ref "U$1") (pin "B41") (pinfunction "GND_B41") (pintype "input"))
      (node (ref "U$1") (pin "B42") (pinfunction "GND_B42") (pintype "input"))
      (node (ref "U$1") (pin "B45") (pinfunction "GND_B45") (pintype "input"))
      (node (ref "U$1") (pin "B46") (pinfunction "GND_B46") (pintype "input"))
      (node (ref "U$1") (pin "B49") (pinfunction "GND/PRSNT2#_B49") (pintype "input"))
      (node (ref "U$1") (pin "B7") (pinfunction "GND_B7") (pintype "input"))
      (node (ref "U$2") (pin "2") (pinfunction "GND_2") (pintype "bidirectional"))
      (node (ref "U$3") (pin "2") (pinfunction "VN_2") (pintype "bidirectional"))
      (node (ref "U$4") (pin "2") (pinfunction "GND_2") (pintype "bidirectional"))
      (node (ref "U$5") (pin "S1") (pinfunction "SHIELD_S1") (pintype "bidirectional"))
      (node (ref "U$5") (pin "S2") (pinfunction "SHIELD_S2") (pintype "bidirectional"))
      (node (ref "U$6") (pin "2") (pinfunction "VN_2") (pintype "bidirectional"))
      (node (ref "U$7") (pin "13") (pinfunction "GND_13") (pintype "bidirectional"))
      (node (ref "U$7") (pin "5") (pinfunction "GND_5") (pintype "bidirectional"))
      (node (ref "U$7") (pin "6") (pinfunction "~{CTS}_6") (pintype "bidirectional"))
      (node (ref "U$8") (pin "5") (pinfunction "GND_5") (pintype "input"))
      (node (ref "U$8") (pin "P$1") (pinfunction "GND_P$1") (pintype "input"))
      (node (ref "U$8") (pin "P$2") (pinfunction "GND_P$2") (pintype "input"))
      (node (ref "U$8") (pin "P$3") (pinfunction "GND_P$3") (pintype "input"))
      (node (ref "U$8") (pin "P$4") (pinfunction "GND_P$4") (pintype "input"))
      (node (ref "U$8") (pin "P$5") (pinfunction "GND_P$5") (pintype "input"))
      (node (ref "U$8") (pin "PAD") (pinfunction "GND_PAD") (pintype "input"))
      (node (ref "U$9") (pin "1") (pinfunction "GND_1") (pintype "input"))
    )
    (net (code "36") (name "Net-(C1-Pad1)") (class "Default")
      (node (ref "C1") (pin "1") (pinfunction "1_1") (pintype "passive"))
      (node (ref "JP1") (pin "MT1") (pinfunction "SHELL_MT1") (pintype "bidirectional"))
      (node (ref "JP1") (pin "MT2") (pinfunction "SHELL_MT2") (pintype "bidirectional"))
      (node (ref "JP1") (pin "P$1") (pinfunction "SHELL_P$1") (pintype "bidirectional"))
      (node (ref "JP1") (pin "P$2") (pinfunction "SHELL_P$2") (pintype "bidirectional"))
      (node (ref "R1") (pin "2") (pinfunction "2_2") (pintype "passive"))
    )
    (net (code "37") (name "Net-(C5-Pad1)") (class "Default")
      (node (ref "C5") (pin "1") (pinfunction "1_1") (pintype "passive"))
      (node (ref "R4") (pin "1") (pinfunction "1_1") (pintype "passive"))
      (node (ref "U$5") (pin "3") (pinfunction "COM_3") (pintype "bidirectional"))
      (node (ref "U$5") (pin "6") (pinfunction "COM_6") (pintype "bidirectional"))
    )
    (net (code "38") (name "Net-(C12-Pad1)") (class "Default")
      (node (ref "C12") (pin "1") (pinfunction "1_1") (pintype "passive"))
      (node (ref "JP2") (pin "MT1") (pinfunction "SHELL_MT1") (pintype "bidirectional"))
      (node (ref "JP2") (pin "MT2") (pinfunction "SHELL_MT2") (pintype "bidirectional"))
      (node (ref "JP2") (pin "P$1") (pinfunction "SHELL_P$1") (pintype "bidirectional"))
      (node (ref "JP2") (pin "P$2") (pinfunction "SHELL_P$2") (pintype "bidirectional"))
      (node (ref "R21") (pin "2") (pinfunction "2_2") (pintype "passive"))
    )
    (net (code "39") (name "Net-(J1-5V_STDBY)") (class "Default")
      (node (ref "J1") (pin "9") (pinfunction "5V_STDBY_9") (pintype "bidirectional"))
      (node (ref "L5VSTD") (pin "A") (pinfunction "A_A") (pintype "passive"))
    )
    (net (code "40") (name "Net-(J1-PS_ON)") (class "Default")
      (node (ref "J1") (pin "16") (pinfunction "PS_ON_16") (pintype "bidirectional"))
      (node (ref "SW_ATXON") (pin "2") (pinfunction "COM0_2") (pintype "bidirectional"))
    )
    (net (code "41") (name "Net-(J1-PWR_OK)") (class "Default")
      (node (ref "J1") (pin "8") (pinfunction "PWR_OK_8") (pintype "bidirectional"))
      (node (ref "LPWROK") (pin "A") (pinfunction "A_A") (pintype "passive"))
    )
    (net (code "42") (name "Net-(L1-1)") (class "Default")
      (node (ref "C18") (pin "2") (pinfunction "2_2") (pintype "passive"))
      (node (ref "L1") (pin "P$1") (pinfunction "1_P$1") (pintype "passive"))
      (node (ref "U$8") (pin "6") (pinfunction "SW_6") (pintype "input"))
    )
    (net (code "43") (name "Net-(L5VSTD-PadC)") (class "Default")
      (node (ref "L5VSTD") (pin "C") (pinfunction "C_C") (pintype "passive"))
      (node (ref "R27") (pin "2") (pinfunction "2_2") (pintype "passive"))
    )
    (net (code "44") (name "Net-(L12V-PadC)") (class "Default")
      (node (ref "L12V") (pin "C") (pinfunction "C_C") (pintype "passive"))
      (node (ref "R14") (pin "2") (pinfunction "2_2") (pintype "passive"))
    )
    (net (code "45") (name "Net-(LPRSNT-PadC)") (class "Default")
      (node (ref "LPRSNT") (pin "C") (pinfunction "C_C") (pintype "passive"))
      (node (ref "R9") (pin "2") (pinfunction "2_2") (pintype "passive"))
    )
    (net (code "46") (name "Net-(LPWROK-PadC)") (class "Default")
      (node (ref "LPWROK") (pin "C") (pinfunction "C_C") (pintype "passive"))
      (node (ref "R7") (pin "2") (pinfunction "2_2") (pintype "passive"))
    )
    (net (code "47") (name "Net-(LPWR_ON-PadA)") (class "Default")
      (node (ref "LPWR_ON") (pin "A") (pinfunction "A_A") (pintype "passive"))
      (node (ref "R13") (pin "1") (pinfunction "1_1") (pintype "passive"))
    )
    (net (code "48") (name "Net-(LRESET-PadC)") (class "Default")
      (node (ref "LRESET") (pin "C") (pinfunction "C_C") (pintype "passive"))
      (node (ref "R16") (pin "2") (pinfunction "2_2") (pintype "passive"))
    )
    (net (code "49") (name "Net-(LRX-PadC)") (class "Default")
      (node (ref "LRX") (pin "C") (pinfunction "C_C") (pintype "passive"))
      (node (ref "R19") (pin "2") (pinfunction "2_2") (pintype "passive"))
    )
    (net (code "50") (name "Net-(LTX-PadC)") (class "Default")
      (node (ref "LTX") (pin "C") (pinfunction "C_C") (pintype "passive"))
      (node (ref "R20") (pin "2") (pinfunction "2_2") (pintype "passive"))
    )
    (net (code "51") (name "Net-(LUBOOT-PadC)") (class "Default")
      (node (ref "LUBOOT") (pin "C") (pinfunction "C_C") (pintype "passive"))
      (node (ref "R18") (pin "2") (pinfunction "2_2") (pintype "passive"))
    )
    (net (code "52") (name "Net-(Q1-D)") (class "Default")
      (node (ref "Q1") (pin "3") (pinfunction "D_3") (pintype "passive"))
      (node (ref "R13") (pin "2") (pinfunction "2_2") (pintype "passive"))
    )
    (net (code "53") (name "Net-(Q1-G)") (class "Default")
      (node (ref "CONN3") (pin "P") (pinfunction "P_P") (pintype "bidirectional"))
      (node (ref "Q1") (pin "1") (pinfunction "G_1") (pintype "passive"))
      (node (ref "R12") (pin "1") (pinfunction "1_1") (pintype "passive"))
      (node (ref "R8") (pin "1") (pinfunction "1_1") (pintype "passive"))
      (node (ref "SW_PWRON") (pin "5") (pinfunction "COM1_5") (pintype "bidirectional"))
      (node (ref "U$1") (pin "B8") (pinfunction "PWR_ON#_B8") (pintype "bidirectional"))
    )
    (net (code "54") (name "Net-(SB1-P$1)") (class "Default")
      (node (ref "SB1") (pin "L1") (pinfunction "P$1_L1") (pintype "passive"))
      (node (ref "U$7") (pin "1") (pinfunction "TXD_1") (pintype "bidirectional"))
    )
    (net (code "55") (name "Net-(SB2-P$1)") (class "Default")
      (node (ref "SB2") (pin "L1") (pinfunction "P$1_L1") (pintype "passive"))
      (node (ref "U$7") (pin "4") (pinfunction "RXD_4") (pintype "bidirectional"))
    )
    (net (code "56") (name "Net-(U$2-ISET)") (class "Default")
      (node (ref "R5") (pin "2") (pinfunction "2_2") (pintype "passive"))
      (node (ref "U$2") (pin "3") (pinfunction "ISET_3") (pintype "bidirectional"))
    )
    (net (code "57") (name "Net-(U$2-OUT)") (class "Default")
      (node (ref "C4") (pin "1") (pinfunction "1_1") (pintype "passive"))
      (node (ref "R26") (pin "2") (pinfunction "2_2") (pintype "passive"))
      (node (ref "SB7") (pin "L1") (pinfunction "P$1_L1") (pintype "passive"))
      (node (ref "SB7") (pin "L2") (pinfunction "P$1_L2") (pintype "passive"))
      (node (ref "U$2") (pin "1") (pinfunction "OUT_1") (pintype "bidirectional"))
    )
    (net (code "58") (name "Net-(U$4-ISET)") (class "Default")
      (node (ref "R10") (pin "2") (pinfunction "2_2") (pintype "passive"))
      (node (ref "U$4") (pin "3") (pinfunction "ISET_3") (pintype "bidirectional"))
    )
    (net (code "59") (name "Net-(U$4-OUT)") (class "Default")
      (node (ref "C8") (pin "1") (pinfunction "1_1") (pintype "passive"))
      (node (ref "R11") (pin "2") (pinfunction "2_2") (pintype "passive"))
      (node (ref "SB6") (pin "L1") (pinfunction "P$1_L1") (pintype "passive"))
      (node (ref "SB6") (pin "L2") (pinfunction "P$1_L2") (pintype "passive"))
      (node (ref "U$4") (pin "1") (pinfunction "OUT_1") (pintype "bidirectional"))
    )
    (net (code "60") (name "Net-(U$7-D+)") (class "Default")
      (node (ref "R22") (pin "2") (pinfunction "2_2") (pintype "passive"))
      (node (ref "U$7") (pin "8") (pinfunction "D+_8") (pintype "bidirectional"))
    )
    (net (code "61") (name "Net-(U$7-D-)") (class "Default")
      (node (ref "R23") (pin "2") (pinfunction "2_2") (pintype "passive"))
      (node (ref "U$7") (pin "9") (pinfunction "D-_9") (pintype "bidirectional"))
    )
    (net (code "62") (name "Net-(U$8-BOOT)") (class "Default")
      (node (ref "C18") (pin "1") (pinfunction "1_1") (pintype "passive"))
      (node (ref "U$8") (pin "7") (pinfunction "BOOT_7") (pintype "input"))
    )
    (net (code "63") (name "Net-(U$8-FB)") (class "Default")
      (node (ref "C21") (pin "2") (pinfunction "2_2") (pintype "passive"))
      (node (ref "R31") (pin "1") (pinfunction "1_1") (pintype "passive"))
      (node (ref "R32") (pin "2") (pinfunction "2_2") (pintype "passive"))
      (node (ref "U$8") (pin "2") (pinfunction "FB_2") (pintype "input"))
    )
    (net (code "64") (name "Net-(U$8-SS)") (class "Default")
      (node (ref "C19") (pin "1") (pinfunction "1_1") (pintype "passive"))
      (node (ref "U$8") (pin "4") (pinfunction "SS_4") (pintype "input"))
    )
    (net (code "65") (name "Net-(U$8-VREG)") (class "Default")
      (node (ref "C20") (pin "1") (pinfunction "1_1") (pintype "passive"))
      (node (ref "U$8") (pin "3") (pinfunction "VREG_3") (pintype "input"))
    )
    (net (code "66") (name "unconnected-(J1--12V-Pad14)") (class "Default")
      (node (ref "J1") (pin "14") (pinfunction "-12V_14") (pintype "bidirectional"))
    )
    (net (code "67") (name "unconnected-(J1-NC-Pad20)") (class "Default")
      (node (ref "J1") (pin "20") (pinfunction "NC_20") (pintype "bidirectional"))
    )
    (net (code "68") (name "unconnected-(JP2-PadID)") (class "Default")
      (node (ref "JP2") (pin "ID") (pinfunction "ID_ID") (pintype "bidirectional"))
    )
    (net (code "69") (name "unconnected-(JP2-PadVBUS)") (class "Default")
      (node (ref "JP2") (pin "VBUS") (pinfunction "VBUS_VBUS") (pintype "bidirectional"))
    )
    (net (code "70") (name "unconnected-(SW_ATXON-COM1-Pad5)") (class "Default")
      (node (ref "SW_ATXON") (pin "5") (pinfunction "COM1_5") (pintype "bidirectional"))
    )
    (net (code "71") (name "unconnected-(SW_ATXON-NC0-Pad1)") (class "Default")
      (node (ref "SW_ATXON") (pin "1") (pinfunction "NC0_1") (pintype "bidirectional"))
    )
    (net (code "72") (name "unconnected-(SW_ATXON-NC1-Pad4)") (class "Default")
      (node (ref "SW_ATXON") (pin "4") (pinfunction "NC1_4") (pintype "bidirectional"))
    )
    (net (code "73") (name "unconnected-(SW_ATXON-NO1-Pad6)") (class "Default")
      (node (ref "SW_ATXON") (pin "6") (pinfunction "NO1_6") (pintype "bidirectional"))
    )
    (net (code "74") (name "unconnected-(SW_PWRON-COM0-Pad2)") (class "Default")
      (node (ref "SW_PWRON") (pin "2") (pinfunction "COM0_2") (pintype "bidirectional"))
    )
    (net (code "75") (name "unconnected-(SW_PWRON-NC0-Pad1)") (class "Default")
      (node (ref "SW_PWRON") (pin "1") (pinfunction "NC0_1") (pintype "bidirectional"))
    )
    (net (code "76") (name "unconnected-(SW_PWRON-NO0-Pad3)") (class "Default")
      (node (ref "SW_PWRON") (pin "3") (pinfunction "NO0_3") (pintype "bidirectional"))
    )
    (net (code "77") (name "unconnected-(SW_PWRON-NO1-Pad6)") (class "Default")
      (node (ref "SW_PWRON") (pin "6") (pinfunction "NO1_6") (pintype "bidirectional"))
    )
    (net (code "78") (name "unconnected-(SW_RESET-Pad1)") (class "Default")
      (node (ref "SW_RESET") (pin "1") (pinfunction "1_1") (pintype "passive"))
    )
    (net (code "79") (name "unconnected-(SW_RESET-Pad4)") (class "Default")
      (node (ref "SW_RESET") (pin "4") (pinfunction "4_4") (pintype "passive"))
    )
    (net (code "80") (name "unconnected-(SW_UBOOT-Pad1)") (class "Default")
      (node (ref "SW_UBOOT") (pin "1") (pinfunction "1_1") (pintype "passive"))
    )
    (net (code "81") (name "unconnected-(SW_UBOOT-Pad4)") (class "Default")
      (node (ref "SW_UBOOT") (pin "4") (pinfunction "4_4") (pintype "passive"))
    )
    (net (code "82") (name "unconnected-(U$1-GND{slash}SVR_ID4-PadA12)") (class "Default")
      (node (ref "U$1") (pin "A12") (pinfunction "GND/SVR_ID4_A12") (pintype "bidirectional"))
    )
    (net (code "83") (name "unconnected-(U$1-I2C_ALERT#-PadB12)") (class "Default")
      (node (ref "U$1") (pin "B12") (pinfunction "I2C_ALERT#_B12") (pintype "bidirectional"))
    )
    (net (code "84") (name "unconnected-(U$1-L2_N-PadA18)") (class "Default")
      (node (ref "U$1") (pin "A18") (pinfunction "L2_N_A18") (pintype "bidirectional"))
    )
    (net (code "85") (name "unconnected-(U$1-L2_P-PadA17)") (class "Default")
      (node (ref "U$1") (pin "A17") (pinfunction "L2_P_A17") (pintype "bidirectional"))
    )
    (net (code "86") (name "unconnected-(U$1-L4_N-PadA22)") (class "Default")
      (node (ref "U$1") (pin "A22") (pinfunction "L4_N_A22") (pintype "bidirectional"))
    )
    (net (code "87") (name "unconnected-(U$1-L4_P-PadA21)") (class "Default")
      (node (ref "U$1") (pin "A21") (pinfunction "L4_P_A21") (pintype "bidirectional"))
    )
    (net (code "88") (name "unconnected-(U$1-L6_N-PadA26)") (class "Default")
      (node (ref "U$1") (pin "A26") (pinfunction "L6_N_A26") (pintype "bidirectional"))
    )
    (net (code "89") (name "unconnected-(U$1-L6_P-PadA25)") (class "Default")
      (node (ref "U$1") (pin "A25") (pinfunction "L6_P_A25") (pintype "bidirectional"))
    )
    (net (code "90") (name "unconnected-(U$1-L8_N-PadA30)") (class "Default")
      (node (ref "U$1") (pin "A30") (pinfunction "L8_N_A30") (pintype "bidirectional"))
    )
    (net (code "91") (name "unconnected-(U$1-L8_P-PadA29)") (class "Default")
      (node (ref "U$1") (pin "A29") (pinfunction "L8_P_A29") (pintype "bidirectional"))
    )
    (net (code "92") (name "unconnected-(U$1-L9_N-PadB32)") (class "Default")
      (node (ref "U$1") (pin "B32") (pinfunction "L9_N_B32") (pintype "bidirectional"))
    )
    (net (code "93") (name "unconnected-(U$1-L9_P-PadB31)") (class "Default")
      (node (ref "U$1") (pin "B31") (pinfunction "L9_P_B31") (pintype "bidirectional"))
    )
    (net (code "94") (name "unconnected-(U$1-L10_N-PadA34)") (class "Default")
      (node (ref "U$1") (pin "A34") (pinfunction "L10_N_A34") (pintype "bidirectional"))
    )
    (net (code "95") (name "unconnected-(U$1-L10_P-PadA33)") (class "Default")
      (node (ref "U$1") (pin "A33") (pinfunction "L10_P_A33") (pintype "bidirectional"))
    )
    (net (code "96") (name "unconnected-(U$1-L11_N-PadB36)") (class "Default")
      (node (ref "U$1") (pin "B36") (pinfunction "L11_N_B36") (pintype "bidirectional"))
    )
    (net (code "97") (name "unconnected-(U$1-L11_P-PadB35)") (class "Default")
      (node (ref "U$1") (pin "B35") (pinfunction "L11_P_B35") (pintype "bidirectional"))
    )
    (net (code "98") (name "unconnected-(U$1-L12_N-PadA38)") (class "Default")
      (node (ref "U$1") (pin "A38") (pinfunction "L12_N_A38") (pintype "bidirectional"))
    )
    (net (code "99") (name "unconnected-(U$1-L12_P-PadA37)") (class "Default")
      (node (ref "U$1") (pin "A37") (pinfunction "L12_P_A37") (pintype "bidirectional"))
    )
    (net (code "100") (name "unconnected-(U$1-L13_N-PadA42)") (class "Default")
      (node (ref "U$1") (pin "A42") (pinfunction "L13_N_A42") (pintype "bidirectional"))
    )
    (net (code "101") (name "unconnected-(U$1-L13_P-PadA41)") (class "Default")
      (node (ref "U$1") (pin "A41") (pinfunction "L13_P_A41") (pintype "bidirectional"))
    )
    (net (code "102") (name "unconnected-(U$1-L14_N-PadA46)") (class "Default")
      (node (ref "U$1") (pin "A46") (pinfunction "L14_N_A46") (pintype "bidirectional"))
    )
    (net (code "103") (name "unconnected-(U$1-L14_P-PadA45)") (class "Default")
      (node (ref "U$1") (pin "A45") (pinfunction "L14_P_A45") (pintype "bidirectional"))
    )
    (net (code "104") (name "unconnected-(U$1-PCIE_RESET#-PadA11)") (class "Default")
      (node (ref "U$1") (pin "A11") (pinfunction "PCIE_RESET#_A11") (pintype "bidirectional"))
    )
    (net (code "105") (name "unconnected-(U$1-RFU-PadA49)") (class "Default")
      (node (ref "U$1") (pin "A49") (pinfunction "RFU_A49") (pintype "no_connect"))
    )
    (net (code "106") (name "unconnected-(U$1-RFU-PadB39)") (class "Default")
      (node (ref "U$1") (pin "B39") (pinfunction "RFU_B39") (pintype "no_connect"))
    )
    (net (code "107") (name "unconnected-(U$1-RFU-PadB40)") (class "Default")
      (node (ref "U$1") (pin "B40") (pinfunction "RFU_B40") (pintype "no_connect"))
    )
    (net (code "108") (name "unconnected-(U$1-SVR_ID0-PadA5)") (class "Default")
      (node (ref "U$1") (pin "A5") (pinfunction "SVR_ID0_A5") (pintype "bidirectional"))
    )
    (net (code "109") (name "unconnected-(U$1-SVR_ID2-PadA9)") (class "Default")
      (node (ref "U$1") (pin "A9") (pinfunction "SVR_ID2_A9") (pintype "bidirectional"))
    )
    (net (code "110") (name "unconnected-(U$3-CH2-Pad3)") (class "Default")
      (node (ref "U$3") (pin "3") (pinfunction "CH2_3") (pintype "bidirectional"))
    )
    (net (code "111") (name "unconnected-(U$5-LGN-PadL4)") (class "Default")
      (node (ref "U$5") (pin "L4") (pinfunction "LGN_L4") (pintype "bidirectional"))
    )
    (net (code "112") (name "unconnected-(U$5-LGP-PadL3)") (class "Default")
      (node (ref "U$5") (pin "L3") (pinfunction "LGP_L3") (pintype "bidirectional"))
    )
    (net (code "113") (name "unconnected-(U$5-LYN-PadL2)") (class "Default")
      (node (ref "U$5") (pin "L2") (pinfunction "LYN_L2") (pintype "bidirectional"))
    )
    (net (code "114") (name "unconnected-(U$5-LYP-PadL1)") (class "Default")
      (node (ref "U$5") (pin "L1") (pinfunction "LYP_L1") (pintype "bidirectional"))
    )
    (net (code "115") (name "unconnected-(U$6-CH1-Pad1)") (class "Default")
      (node (ref "U$6") (pin "1") (pinfunction "CH1_1") (pintype "bidirectional"))
    )
    (net (code "116") (name "unconnected-(U$6-CH2-Pad3)") (class "Default")
      (node (ref "U$6") (pin "3") (pinfunction "CH2_3") (pintype "bidirectional"))
    )
    (net (code "117") (name "unconnected-(U$7-CBUS0-Pad15)") (class "Default")
      (node (ref "U$7") (pin "15") (pinfunction "CBUS0_15") (pintype "bidirectional"))
    )
    (net (code "118") (name "unconnected-(U$7-CBUS3-Pad16)") (class "Default")
      (node (ref "U$7") (pin "16") (pinfunction "CBUS3_16") (pintype "bidirectional"))
    )
    (net (code "119") (name "unconnected-(U$7-~{RESET}-Pad11)") (class "Default")
      (node (ref "U$7") (pin "11") (pinfunction "~{RESET}_11") (pintype "bidirectional"))
    )
    (net (code "120") (name "unconnected-(U$7-~{RTS}-Pad2)") (class "Default")
      (node (ref "U$7") (pin "2") (pinfunction "~{RTS}_2") (pintype "bidirectional"))
    )
  )
)
